# arduinizer.net
KiCad netlist of a schematic drawn in EAGLE
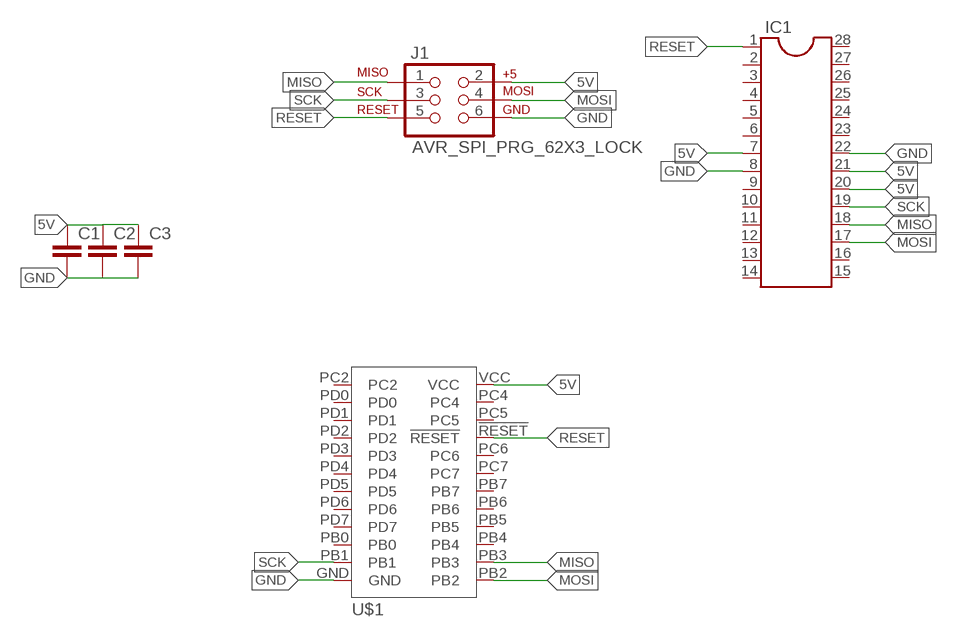
[diagram p0: schematic, sheet 1]

(export (version "E")
  (design (tool "Eeschema 10.0.6"))
  (components
    (comp (ref "C1")
      (value "C-EU025-025X050")
      (footprint "eagle-import:C025-025X050")
      (libsource (lib "eagle-import") (part "C-EU025-025X050"))
    )
    (comp (ref "C2")
      (value "C-EU025-025X050")
      (footprint "eagle-import:C025-025X050")
      (libsource (lib "eagle-import") (part "C-EU025-025X050"))
    )
    (comp (ref "C3")
      (value "C-EU025-025X050")
      (footprint "eagle-import:C025-025X050")
      (libsource (lib "eagle-import") (part "C-EU025-025X050"))
    )
    (comp (ref "IC1")
      (value "DIL28")
      (footprint "eagle-import:DIL28-6")
      (libsource (lib "eagle-import") (part "DIL28"))
    )
    (comp (ref "J1")
      (value "AVR_SPI_PRG_62X3_LOCK")
      (footprint "eagle-import:2X3_LOCK")
      (libsource (lib "eagle-import") (part "AVR_SPI_PRG_62X3_LOCK"))
    )
    (comp (ref "U$1")
      (value "MINIMUSBIGPADS")
      (footprint "eagle-import:MINIMUSBIGPADS")
      (libsource (lib "eagle-import") (part "MINIMUSBIGPADS"))
    )
  )
  (nets
    (net (code "1") (name "5V") (class "Default")
      (node (ref "C1") (pin "1") (pinfunction "1_1") (pintype "passive"))
      (node (ref "C2") (pin "1") (pinfunction "1_1") (pintype "passive"))
      (node (ref "C3") (pin "1") (pinfunction "1_1") (pintype "passive"))
      (node (ref "IC1") (pin "20") (pinfunction "20_20") (pintype "passive"))
      (node (ref "IC1") (pin "21") (pinfunction "21_21") (pintype "passive"))
      (node (ref "IC1") (pin "7") (pinfunction "7_7") (pintype "passive"))
      (node (ref "J1") (pin "2") (pinfunction "2_2") (pintype "passive"))
      (node (ref "U$1") (pin "VCC") (pinfunction "VCC_VCC") (pintype "power_in"))
    )
    (net (code "2") (name "GND") (class "Default")
      (node (ref "C1") (pin "2") (pinfunction "2_2") (pintype "passive"))
      (node (ref "C2") (pin "2") (pinfunction "2_2") (pintype "passive"))
      (node (ref "C3") (pin "2") (pinfunction "2_2") (pintype "passive"))
      (node (ref "IC1") (pin "22") (pinfunction "22_22") (pintype "passive"))
      (node (ref "IC1") (pin "8") (pinfunction "8_8") (pintype "passive"))
      (node (ref "J1") (pin "6") (pinfunction "6_6") (pintype "passive"))
      (node (ref "U$1") (pin "GND") (pinfunction "GND_GND") (pintype "power_in"))
    )
    (net (code "3") (name "MISO") (class "Default")
      (node (ref "IC1") (pin "18") (pinfunction "18_18") (pintype "passive"))
      (node (ref "J1") (pin "1") (pinfunction "1_1") (pintype "passive"))
      (node (ref "U$1") (pin "PB3") (pinfunction "PB3_PB3") (pintype "bidirectional"))
    )
    (net (code "4") (name "MOSI") (class "Default")
      (node (ref "IC1") (pin "17") (pinfunction "17_17") (pintype "passive"))
      (node (ref "J1") (pin "4") (pinfunction "4_4") (pintype "passive"))
      (node (ref "U$1") (pin "PB2") (pinfunction "PB2_PB2") (pintype "bidirectional"))
    )
    (net (code "5") (name "RESET") (class "Default")
      (node (ref "IC1") (pin "1") (pinfunction "1_1") (pintype "passive"))
      (node (ref "J1") (pin "5") (pinfunction "5_5") (pintype "passive"))
      (node (ref "U$1") (pin "!RESET") (pinfunction "~{RESET}_!RESET") (pintype "input"))
    )
    (net (code "6") (name "SCK") (class "Default")
      (node (ref "IC1") (pin "19") (pinfunction "19_19") (pintype "passive"))
      (node (ref "J1") (pin "3") (pinfunction "3_3") (pintype "passive"))
      (node (ref "U$1") (pin "PB1") (pinfunction "PB1_PB1") (pintype "bidirectional"))
    )
    (net (code "7") (name "unconnected-(IC1-Pad2)") (class "Default")
      (node (ref "IC1") (pin "2") (pinfunction "2_2") (pintype "passive"))
    )
    (net (code "8") (name "unconnected-(IC1-Pad3)") (class "Default")
      (node (ref "IC1") (pin "3") (pinfunction "3_3") (pintype "passive"))
    )
    (net (code "9") (name "unconnected-(IC1-Pad4)") (class "Default")
      (node (ref "IC1") (pin "4") (pinfunction "4_4") (pintype "passive"))
    )
    (net (code "10") (name "unconnected-(IC1-Pad5)") (class "Default")
      (node (ref "IC1") (pin "5") (pinfunction "5_5") (pintype "passive"))
    )
    (net (code "11") (name "unconnected-(IC1-Pad6)") (class "Default")
      (node (ref "IC1") (pin "6") (pinfunction "6_6") (pintype "passive"))
    )
    (net (code "12") (name "unconnected-(IC1-Pad9)") (class "Default")
      (node (ref "IC1") (pin "9") (pinfunction "9_9") (pintype "passive"))
    )
    (net (code "13") (name "unconnected-(IC1-Pad10)") (class "Default")
      (node (ref "IC1") (pin "10") (pinfunction "10_10") (pintype "passive"))
    )
    (net (code "14") (name "unconnected-(IC1-Pad11)") (class "Default")
      (node (ref "IC1") (pin "11") (pinfunction "11_11") (pintype "passive"))
    )
    (net (code "15") (name "unconnected-(IC1-Pad12)") (class "Default")
      (node (ref "IC1") (pin "12") (pinfunction "12_12") (pintype "passive"))
    )
    (net (code "16") (name "unconnected-(IC1-Pad13)") (class "Default")
      (node (ref "IC1") (pin "13") (pinfunction "13_13") (pintype "passive"))
    )
    (net (code "17") (name "unconnected-(IC1-Pad14)") (class "Default")
      (node (ref "IC1") (pin "14") (pinfunction "14_14") (pintype "passive"))
    )
    (net (code "18") (name "unconnected-(IC1-Pad15)") (class "Default")
      (node (ref "IC1") (pin "15") (pinfunction "15_15") (pintype "passive"))
    )
    (net (code "19") (name "unconnected-(IC1-Pad16)") (class "Default")
      (node (ref "IC1") (pin "16") (pinfunction "16_16") (pintype "passive"))
    )
    (net (code "20") (name "unconnected-(IC1-Pad23)") (class "Default")
      (node (ref "IC1") (pin "23") (pinfunction "23_23") (pintype "passive"))
    )
    (net (code "21") (name "unconnected-(IC1-Pad24)") (class "Default")
      (node (ref "IC1") (pin "24") (pinfunction "24_24") (pintype "passive"))
    )
    (net (code "22") (name "unconnected-(IC1-Pad25)") (class "Default")
      (node (ref "IC1") (pin "25") (pinfunction "25_25") (pintype "passive"))
    )
    (net (code "23") (name "unconnected-(IC1-Pad26)") (class "Default")
      (node (ref "IC1") (pin "26") (pinfunction "26_26") (pintype "passive"))
    )
    (net (code "24") (name "unconnected-(IC1-Pad27)") (class "Default")
      (node (ref "IC1") (pin "27") (pinfunction "27_27") (pintype "passive"))
    )
    (net (code "25") (name "unconnected-(IC1-Pad28)") (class "Default")
      (node (ref "IC1") (pin "28") (pinfunction "28_28") (pintype "passive"))
    )
    (net (code "26") (name "unconnected-(U$1-PadPB0)") (class "Default")
      (node (ref "U$1") (pin "PB0") (pinfunction "PB0_PB0") (pintype "bidirectional"))
    )
    (net (code "27") (name "unconnected-(U$1-PadPB4)") (class "Default")
      (node (ref "U$1") (pin "PB4") (pinfunction "PB4_PB4") (pintype "bidirectional"))
    )
    (net (code "28") (name "unconnected-(U$1-PadPB5)") (class "Default")
      (node (ref "U$1") (pin "PB5") (pinfunction "PB5_PB5") (pintype "bidirectional"))
    )
    (net (code "29") (name "unconnected-(U$1-PadPB6)") (class "Default")
      (node (ref "U$1") (pin "PB6") (pinfunction "PB6_PB6") (pintype "bidirectional"))
    )
    (net (code "30") (name "unconnected-(U$1-PadPB7)") (class "Default")
      (node (ref "U$1") (pin "PB7") (pinfunction "PB7_PB7") (pintype "bidirectional"))
    )
    (net (code "31") (name "unconnected-(U$1-PadPC2)") (class "Default")
      (node (ref "U$1") (pin "PC2") (pinfunction "PC2_PC2") (pintype "bidirectional"))
    )
    (net (code "32") (name "unconnected-(U$1-PadPC4)") (class "Default")
      (node (ref "U$1") (pin "PC4") (pinfunction "PC4_PC4") (pintype "bidirectional"))
    )
    (net (code "33") (name "unconnected-(U$1-PadPC5)") (class "Default")
      (node (ref "U$1") (pin "PC5") (pinfunction "PC5_PC5") (pintype "bidirectional"))
    )
    (net (code "34") (name "unconnected-(U$1-PadPC6)") (class "Default")
      (node (ref "U$1") (pin "PC6") (pinfunction "PC6_PC6") (pintype "bidirectional"))
    )
    (net (code "35") (name "unconnected-(U$1-PadPC7)") (class "Default")
      (node (ref "U$1") (pin "PC7") (pinfunction "PC7_PC7") (pintype "bidirectional"))
    )
    (net (code "36") (name "unconnected-(U$1-PadPD0)") (class "Default")
      (node (ref "U$1") (pin "PD0") (pinfunction "PD0_PD0") (pintype "bidirectional"))
    )
    (net (code "37") (name "unconnected-(U$1-PadPD1)") (class "Default")
      (node (ref "U$1") (pin "PD1") (pinfunction "PD1_PD1") (pintype "bidirectional"))
    )
    (net (code "38") (name "unconnected-(U$1-PadPD2)") (class "Default")
      (node (ref "U$1") (pin "PD2") (pinfunction "PD2_PD2") (pintype "bidirectional"))
    )
    (net (code "39") (name "unconnected-(U$1-PadPD3)") (class "Default")
      (node (ref "U$1") (pin "PD3") (pinfunction "PD3_PD3") (pintype "bidirectional"))
    )
    (net (code "40") (name "unconnected-(U$1-PadPD4)") (class "Default")
      (node (ref "U$1") (pin "PD4") (pinfunction "PD4_PD4") (pintype "bidirectional"))
    )
    (net (code "41") (name "unconnected-(U$1-PadPD5)") (class "Default")
      (node (ref "U$1") (pin "PD5") (pinfunction "PD5_PD5") (pintype "bidirectional"))
    )
    (net (code "42") (name "unconnected-(U$1-PadPD6)") (class "Default")
      (node (ref "U$1") (pin "PD6") (pinfunction "PD6_PD6") (pintype "bidirectional"))
    )
    (net (code "43") (name "unconnected-(U$1-PadPD7)") (class "Default")
      (node (ref "U$1") (pin "PD7") (pinfunction "PD7_PD7") (pintype "bidirectional"))
    )
  )
)
